# 4_waffling60-DB_periferals.net
KiCad netlist of a schematic drawn in Altium Designer
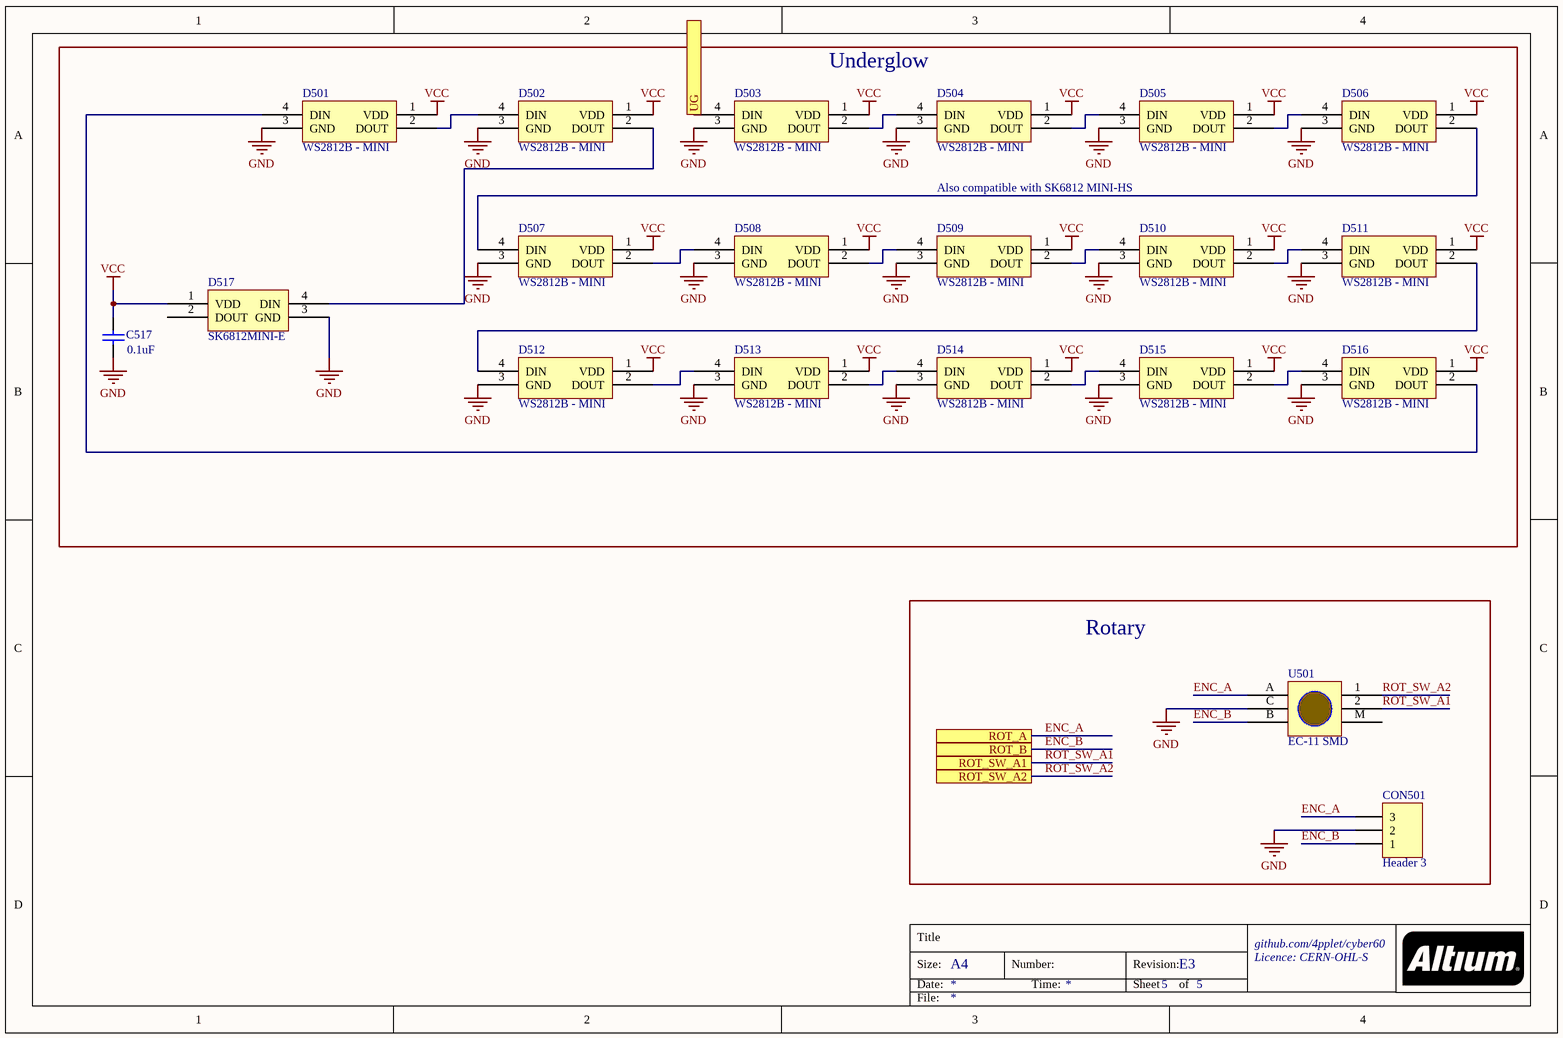
[diagram p0: 4_waffling60-DB_periferals.SchDoc]

(export (version "E")
  (design (tool "Eeschema 10.0.6"))
  (components
    (comp (ref "C517")
      (value "0.1uF")
      (footprint "C0603[1608]")
      (description "Capacitor")
      (fields (field (name "LCSC PART #") "C14663") (field (name "MRF.PART") "CC0603KRX7R9BB104"))
      (libsource (lib "Miscellaneous Devices") (part "Cap"))
    )
    (comp (ref "CON501")
      (value "Header 3")
      (footprint "HDR1X3")
      (description "Header, 3-Pin")
      (libsource (lib "Miscellaneous Connectors") (part "Header 3"))
    )
    (comp (ref "D501")
      (value "WS2812B - MINI")
      (footprint "WS2812B - 2020")
      (fields (field (name "LCSC PART #") "C965555") (field (name "MRF.PART") "WS2812B-2020"))
      (libsource (lib "Keebs") (part "WS2812B"))
    )
    (comp (ref "D502")
      (value "WS2812B - MINI")
      (footprint "WS2812B - 2020")
      (fields (field (name "LCSC PART #") "C965555") (field (name "MRF.PART") "WS2812B-2020"))
      (libsource (lib "Keebs") (part "WS2812B"))
    )
    (comp (ref "D503")
      (value "WS2812B - MINI")
      (footprint "WS2812B - 2020")
      (fields (field (name "LCSC PART #") "C965555") (field (name "MRF.PART") "WS2812B-2020"))
      (libsource (lib "Keebs") (part "WS2812B"))
    )
    (comp (ref "D504")
      (value "WS2812B - MINI")
      (footprint "WS2812B - 2020")
      (fields (field (name "LCSC PART #") "C965555") (field (name "MRF.PART") "WS2812B-2020"))
      (libsource (lib "Keebs") (part "WS2812B"))
    )
    (comp (ref "D505")
      (value "WS2812B - MINI")
      (footprint "WS2812B - 2020")
      (fields (field (name "LCSC PART #") "C965555") (field (name "MRF.PART") "WS2812B-2020"))
      (libsource (lib "Keebs") (part "WS2812B"))
    )
    (comp (ref "D506")
      (value "WS2812B - MINI")
      (footprint "WS2812B - 2020")
      (fields (field (name "LCSC PART #") "C965555") (field (name "MRF.PART") "WS2812B-2020"))
      (libsource (lib "Keebs") (part "WS2812B"))
    )
    (comp (ref "D507")
      (value "WS2812B - MINI")
      (footprint "WS2812B - 2020")
      (fields (field (name "LCSC PART #") "C965555") (field (name "MRF.PART") "WS2812B-2020"))
      (libsource (lib "Keebs") (part "WS2812B"))
    )
    (comp (ref "D508")
      (value "WS2812B - MINI")
      (footprint "WS2812B - 2020")
      (fields (field (name "LCSC PART #") "C965555") (field (name "MRF.PART") "WS2812B-2020"))
      (libsource (lib "Keebs") (part "WS2812B"))
    )
    (comp (ref "D509")
      (value "WS2812B - MINI")
      (footprint "WS2812B - 2020")
      (fields (field (name "LCSC PART #") "C965555") (field (name "MRF.PART") "WS2812B-2020"))
      (libsource (lib "Keebs") (part "WS2812B"))
    )
    (comp (ref "D510")
      (value "WS2812B - MINI")
      (footprint "WS2812B - 2020")
      (fields (field (name "LCSC PART #") "C965555") (field (name "MRF.PART") "WS2812B-2020"))
      (libsource (lib "Keebs") (part "WS2812B"))
    )
    (comp (ref "D511")
      (value "WS2812B - MINI")
      (footprint "WS2812B - 2020")
      (fields (field (name "LCSC PART #") "C965555") (field (name "MRF.PART") "WS2812B-2020"))
      (libsource (lib "Keebs") (part "WS2812B"))
    )
    (comp (ref "D512")
      (value "WS2812B - MINI")
      (footprint "WS2812B - 2020")
      (fields (field (name "LCSC PART #") "C965555") (field (name "MRF.PART") "WS2812B-2020"))
      (libsource (lib "Keebs") (part "WS2812B"))
    )
    (comp (ref "D513")
      (value "WS2812B - MINI")
      (footprint "WS2812B - 2020")
      (fields (field (name "LCSC PART #") "C965555") (field (name "MRF.PART") "WS2812B-2020"))
      (libsource (lib "Keebs") (part "WS2812B"))
    )
    (comp (ref "D514")
      (value "WS2812B - MINI")
      (footprint "WS2812B - 2020")
      (fields (field (name "LCSC PART #") "C965555") (field (name "MRF.PART") "WS2812B-2020"))
      (libsource (lib "Keebs") (part "WS2812B"))
    )
    (comp (ref "D515")
      (value "WS2812B - MINI")
      (footprint "WS2812B - 2020")
      (fields (field (name "LCSC PART #") "C965555") (field (name "MRF.PART") "WS2812B-2020"))
      (libsource (lib "Keebs") (part "WS2812B"))
    )
    (comp (ref "D516")
      (value "WS2812B - MINI")
      (footprint "WS2812B - 2020")
      (fields (field (name "LCSC PART #") "C965555") (field (name "MRF.PART") "WS2812B-2020"))
      (libsource (lib "Keebs") (part "WS2812B"))
    )
    (comp (ref "D517")
      (value "SK6812MINI-E")
      (footprint "SK6812MINI-E - shaped")
      (fields (field (name "LCSC PART #") "C524051") (field (name "MRF.PART") "DY-S352818/RGBC/6812-2T"))
      (libsource (lib "Keebs") (part "SK6812MINI-E"))
    )
    (comp (ref "U501") (value "EC-11 SMD") (footprint "EC11-SMD") (libsource (lib "Keebs") (part "EC-11")))
  )
  (nets
    (net (code "1") (name "/ENC_A") (class "Default")
      (node (ref "CON501") (pin "3") (pinfunction "3_3") (pintype "passive"))
      (node (ref "U501") (pin "A") (pinfunction "B_A") (pintype "passive"))
    )
    (net (code "2") (name "/ENC_B") (class "Default")
      (node (ref "CON501") (pin "1") (pinfunction "1_1") (pintype "passive"))
      (node (ref "U501") (pin "B") (pinfunction "B_B") (pintype "passive"))
    )
    (net (code "3") (name "/ROT_SW_A1") (class "Default")
      (node (ref "U501") (pin "2") (pinfunction "2_2") (pintype "passive"))
    )
    (net (code "4") (name "/ROT_SW_A2") (class "Default")
      (node (ref "U501") (pin "1") (pinfunction "1_1") (pintype "passive"))
    )
    (net (code "5") (name "/UG") (class "Default")
      (node (ref "D503") (pin "4") (pinfunction "DIN_4") (pintype "passive"))
    )
    (net (code "6") (name "GND") (class "Default")
      (node (ref "C517") (pin "1") (pinfunction "1_1") (pintype "passive"))
      (node (ref "CON501") (pin "2") (pinfunction "2_2") (pintype "passive"))
      (node (ref "D501") (pin "3") (pinfunction "GND_3") (pintype "passive"))
      (node (ref "D502") (pin "3") (pinfunction "GND_3") (pintype "passive"))
      (node (ref "D503") (pin "3") (pinfunction "GND_3") (pintype "passive"))
      (node (ref "D504") (pin "3") (pinfunction "GND_3") (pintype "passive"))
      (node (ref "D505") (pin "3") (pinfunction "GND_3") (pintype "passive"))
      (node (ref "D506") (pin "3") (pinfunction "GND_3") (pintype "passive"))
      (node (ref "D507") (pin "3") (pinfunction "GND_3") (pintype "passive"))
      (node (ref "D508") (pin "3") (pinfunction "GND_3") (pintype "passive"))
      (node (ref "D509") (pin "3") (pinfunction "GND_3") (pintype "passive"))
      (node (ref "D510") (pin "3") (pinfunction "GND_3") (pintype "passive"))
      (node (ref "D511") (pin "3") (pinfunction "GND_3") (pintype "passive"))
      (node (ref "D512") (pin "3") (pinfunction "GND_3") (pintype "passive"))
      (node (ref "D513") (pin "3") (pinfunction "GND_3") (pintype "passive"))
      (node (ref "D514") (pin "3") (pinfunction "GND_3") (pintype "passive"))
      (node (ref "D515") (pin "3") (pinfunction "GND_3") (pintype "passive"))
      (node (ref "D516") (pin "3") (pinfunction "GND_3") (pintype "passive"))
      (node (ref "D517") (pin "3") (pinfunction "GND_3") (pintype "passive"))
      (node (ref "U501") (pin "C") (pinfunction "C_C") (pintype "passive"))
    )
    (net (code "7") (name "Net-(D501-DIN)") (class "Default")
      (node (ref "D501") (pin "4") (pinfunction "DIN_4") (pintype "passive"))
      (node (ref "D516") (pin "2") (pinfunction "DOUT_2") (pintype "passive"))
    )
    (net (code "8") (name "Net-(D501-DOUT)") (class "Default")
      (node (ref "D501") (pin "2") (pinfunction "DOUT_2") (pintype "passive"))
      (node (ref "D502") (pin "4") (pinfunction "DIN_4") (pintype "passive"))
    )
    (net (code "9") (name "Net-(D502-DOUT)") (class "Default")
      (node (ref "D502") (pin "2") (pinfunction "DOUT_2") (pintype "passive"))
      (node (ref "D517") (pin "4") (pinfunction "DIN_4") (pintype "passive"))
    )
    (net (code "10") (name "Net-(D503-DOUT)") (class "Default")
      (node (ref "D503") (pin "2") (pinfunction "DOUT_2") (pintype "passive"))
      (node (ref "D504") (pin "4") (pinfunction "DIN_4") (pintype "passive"))
    )
    (net (code "11") (name "Net-(D504-DOUT)") (class "Default")
      (node (ref "D504") (pin "2") (pinfunction "DOUT_2") (pintype "passive"))
      (node (ref "D505") (pin "4") (pinfunction "DIN_4") (pintype "passive"))
    )
    (net (code "12") (name "Net-(D505-DOUT)") (class "Default")
      (node (ref "D505") (pin "2") (pinfunction "DOUT_2") (pintype "passive"))
      (node (ref "D506") (pin "4") (pinfunction "DIN_4") (pintype "passive"))
    )
    (net (code "13") (name "Net-(D506-DOUT)") (class "Default")
      (node (ref "D506") (pin "2") (pinfunction "DOUT_2") (pintype "passive"))
      (node (ref "D507") (pin "4") (pinfunction "DIN_4") (pintype "passive"))
    )
    (net (code "14") (name "Net-(D507-DOUT)") (class "Default")
      (node (ref "D507") (pin "2") (pinfunction "DOUT_2") (pintype "passive"))
      (node (ref "D508") (pin "4") (pinfunction "DIN_4") (pintype "passive"))
    )
    (net (code "15") (name "Net-(D508-DOUT)") (class "Default")
      (node (ref "D508") (pin "2") (pinfunction "DOUT_2") (pintype "passive"))
      (node (ref "D509") (pin "4") (pinfunction "DIN_4") (pintype "passive"))
    )
    (net (code "16") (name "Net-(D509-DOUT)") (class "Default")
      (node (ref "D509") (pin "2") (pinfunction "DOUT_2") (pintype "passive"))
      (node (ref "D510") (pin "4") (pinfunction "DIN_4") (pintype "passive"))
    )
    (net (code "17") (name "Net-(D510-DOUT)") (class "Default")
      (node (ref "D510") (pin "2") (pinfunction "DOUT_2") (pintype "passive"))
      (node (ref "D511") (pin "4") (pinfunction "DIN_4") (pintype "passive"))
    )
    (net (code "18") (name "Net-(D511-DOUT)") (class "Default")
      (node (ref "D511") (pin "2") (pinfunction "DOUT_2") (pintype "passive"))
      (node (ref "D512") (pin "4") (pinfunction "DIN_4") (pintype "passive"))
    )
    (net (code "19") (name "Net-(D512-DOUT)") (class "Default")
      (node (ref "D512") (pin "2") (pinfunction "DOUT_2") (pintype "passive"))
      (node (ref "D513") (pin "4") (pinfunction "DIN_4") (pintype "passive"))
    )
    (net (code "20") (name "Net-(D513-DOUT)") (class "Default")
      (node (ref "D513") (pin "2") (pinfunction "DOUT_2") (pintype "passive"))
      (node (ref "D514") (pin "4") (pinfunction "DIN_4") (pintype "passive"))
    )
    (net (code "21") (name "Net-(D514-DOUT)") (class "Default")
      (node (ref "D514") (pin "2") (pinfunction "DOUT_2") (pintype "passive"))
      (node (ref "D515") (pin "4") (pinfunction "DIN_4") (pintype "passive"))
    )
    (net (code "22") (name "Net-(D515-DOUT)") (class "Default")
      (node (ref "D515") (pin "2") (pinfunction "DOUT_2") (pintype "passive"))
      (node (ref "D516") (pin "4") (pinfunction "DIN_4") (pintype "passive"))
    )
    (net (code "23") (name "VCC") (class "Default")
      (node (ref "C517") (pin "2") (pinfunction "2_2") (pintype "passive"))
      (node (ref "D501") (pin "1") (pinfunction "VDD_1") (pintype "passive"))
      (node (ref "D502") (pin "1") (pinfunction "VDD_1") (pintype "passive"))
      (node (ref "D503") (pin "1") (pinfunction "VDD_1") (pintype "passive"))
      (node (ref "D504") (pin "1") (pinfunction "VDD_1") (pintype "passive"))
      (node (ref "D505") (pin "1") (pinfunction "VDD_1") (pintype "passive"))
      (node (ref "D506") (pin "1") (pinfunction "VDD_1") (pintype "passive"))
      (node (ref "D507") (pin "1") (pinfunction "VDD_1") (pintype "passive"))
      (node (ref "D508") (pin "1") (pinfunction "VDD_1") (pintype "passive"))
      (node (ref "D509") (pin "1") (pinfunction "VDD_1") (pintype "passive"))
      (node (ref "D510") (pin "1") (pinfunction "VDD_1") (pintype "passive"))
      (node (ref "D511") (pin "1") (pinfunction "VDD_1") (pintype "passive"))
      (node (ref "D512") (pin "1") (pinfunction "VDD_1") (pintype "passive"))
      (node (ref "D513") (pin "1") (pinfunction "VDD_1") (pintype "passive"))
      (node (ref "D514") (pin "1") (pinfunction "VDD_1") (pintype "passive"))
      (node (ref "D515") (pin "1") (pinfunction "VDD_1") (pintype "passive"))
      (node (ref "D516") (pin "1") (pinfunction "VDD_1") (pintype "passive"))
      (node (ref "D517") (pin "1") (pinfunction "VDD_1") (pintype "passive"))
    )
    (net (code "24") (name "unconnected-(D517-DOUT-Pad2)") (class "Default")
      (node (ref "D517") (pin "2") (pinfunction "DOUT_2") (pintype "passive"))
    )
    (net (code "25") (name "unconnected-(U501-PadM)") (class "Default")
      (node (ref "U501") (pin "M") (pinfunction "M_M") (pintype "passive"))
    )
  )
)
